# zb_16f628a.net
KiCad netlist of a schematic drawn in Altium Designer
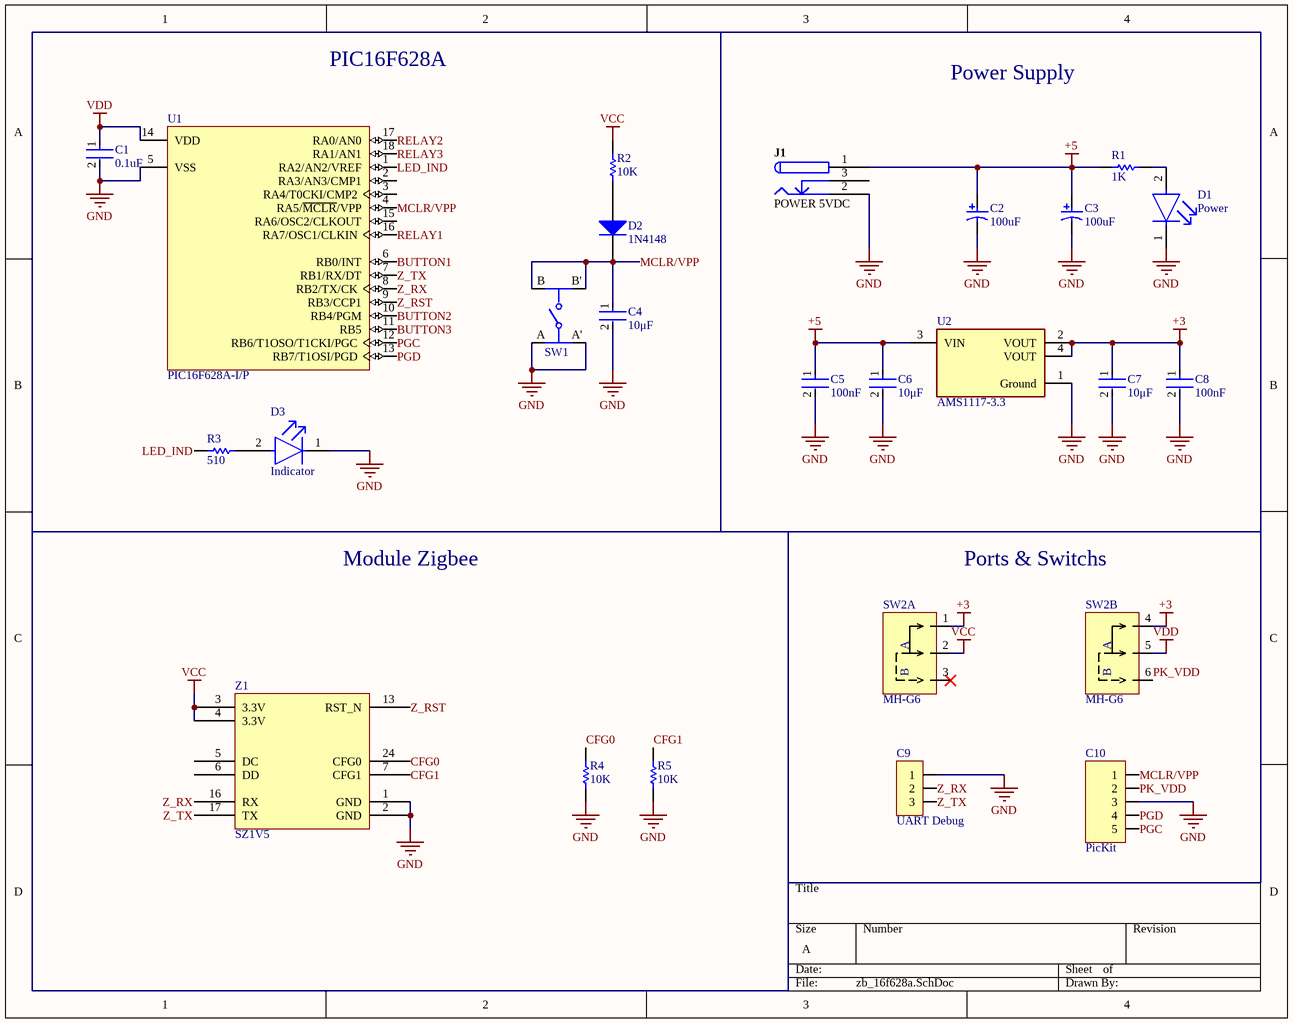
[diagram p0: zb_16f628a.SchDoc]

(export (version "E")
  (design (tool "Eeschema 10.0.6"))
  (components
    (comp (ref "C1")
      (value "0.1uF")
      (footprint "FP-0603-L_1_6_0_15-W_0_81-MFG")
      (description "General Purpose Ceramic Capacitor, 0603, 100nF, 10%, X7R, 15%, 50V")
      (fields (field (name "TOLERANCE") "10%") (field (name "VOLTAGE") "50V"))
      (libsource (lib "Altium Content Vault") (part "02cd4be3c70576c341d710602a673aa"))
    )
    (comp (ref "C2")
      (value "100uF")
      (footprint "PNSC-FK-V-D8_V")
      (fields (field (name "MANUFACTURER") "Panasonic"))
      (libsource (lib "Altium Content Vault") (part "CAP-P-2"))
    )
    (comp (ref "C3")
      (value "100uF")
      (footprint "PNSC-FK-V-D8_V")
      (fields (field (name "MANUFACTURER") "Panasonic"))
      (libsource (lib "Altium Content Vault") (part "CAP-P-2"))
    )
    (comp (ref "C4")
      (value "10μF")
      (footprint "FP-0603-L_1_6_0_15-W_0_81-IPC_A")
      (description "General Purpose Ceramic Capacitor, 0603, 100nF, 10%, X7R, 15%, 50V")
      (fields (field (name "TOLERANCE") "10%") (field (name "VOLTAGE") "50V"))
      (libsource (lib "Altium Content Vault") (part "02cd4be3c70576c341d710602a673aa"))
    )
    (comp (ref "C5")
      (value "100nF")
      (footprint "FP-0603-L_1_6_0_15-W_0_81-IPC_A")
      (description "General Purpose Ceramic Capacitor, 0603, 100nF, 10%, X7R, 15%, 50V")
      (fields (field (name "TOLERANCE") "10%") (field (name "VOLTAGE") "50V"))
      (libsource (lib "Altium Content Vault") (part "02cd4be3c70576c341d710602a673aa"))
    )
    (comp (ref "C6")
      (value "10μF")
      (footprint "FP-0603-L_1_6_0_15-W_0_81-IPC_A")
      (description "General Purpose Ceramic Capacitor, 0603, 100nF, 10%, X7R, 15%, 50V")
      (fields (field (name "TOLERANCE") "10%") (field (name "VOLTAGE") "50V"))
      (libsource (lib "Altium Content Vault") (part "02cd4be3c70576c341d710602a673aa"))
    )
    (comp (ref "C7")
      (value "10μF")
      (footprint "FP-0603-L_1_6_0_15-W_0_81-IPC_A")
      (description "General Purpose Ceramic Capacitor, 0603, 100nF, 10%, X7R, 15%, 50V")
      (fields (field (name "TOLERANCE") "10%") (field (name "VOLTAGE") "50V"))
      (libsource (lib "Altium Content Vault") (part "02cd4be3c70576c341d710602a673aa"))
    )
    (comp (ref "C8")
      (value "100nF")
      (footprint "FP-0603-L_1_6_0_15-W_0_81-IPC_A")
      (description "General Purpose Ceramic Capacitor, 0603, 100nF, 10%, X7R, 15%, 50V")
      (fields (field (name "TOLERANCE") "10%") (field (name "VOLTAGE") "50V"))
      (libsource (lib "Altium Content Vault") (part "02cd4be3c70576c341d710602a673aa"))
    )
    (comp (ref "C9")
      (value "UART Debug")
      (footprint "JP3-D1C")
      (description "WR-PHD 2.54 mm Angled Socket Header")
      (fields
        (field (name "MANUFACTURER") "Würth Elektronik eiSos GmbH")
        (field (name "PARTNO") "613003143121")
        (field (name "CREATED BY") "Karrer Zheng")
      )
      (libsource (lib "TechMT.VN_Lib_Project v2") (part "JP3"))
    )
    (comp (ref "C10")
      (value "PicKit")
      (footprint "JP5-D1C")
      (description "WR-PHD 2.54 mm Angled Socket Header")
      (fields
        (field (name "MANUFACTURER") "Würth Elektronik eiSos GmbH")
        (field (name "PARTNO") "613005143121")
        (field (name "CREATED BY") "Karrer Zheng")
      )
      (libsource (lib "TechMT.VN_Lib_Project v2") (part "JP5"))
    )
    (comp (ref "D1")
      (value "Power")
      (footprint "FP-HLMP-4700-MFG")
      (description "LED RED DIFFUSED T-1 3/4 T/H")
      (fields
        (field (name "OCTOPART") "https://octopart.com/hlmp-4700-broadcom-71130526")
        (field (name "MANUFACTURER") "Broadcom")
      )
      (libsource (lib "Altium Content Vault") (part "8706943c75ba83719d021d2fdc84c58"))
    )
    (comp (ref "D2")
      (value "1N4148")
      (footprint "NXP-SOD27-2_V")
      (description "High-speed Diode, 100 V, 450 mA, 2-Pin SOD27, RoHS")
      (fields (field (name "MANUFACTURER") "NXP Semiconductors"))
      (libsource (lib "Altium Content Vault") (part "NXP-A1K2-2"))
    )
    (comp (ref "D3")
      (value "Indicator")
      (footprint "FP-HLMP-4700-MFG")
      (description "LED RED DIFFUSED T-1 3/4 T/H")
      (fields
        (field (name "OCTOPART") "https://octopart.com/hlmp-4700-broadcom-71130526")
        (field (name "MANUFACTURER") "Broadcom")
      )
      (libsource (lib "Altium Content Vault") (part "8706943c75ba83719d021d2fdc84c58"))
    )
    (comp (ref "J1")
      (value "POWER 5VDC")
      (footprint "KYCN-KLDX-0202-B_V")
      (description "3 Conductor Power Jack, 2 break 2 aux contacts")
      (fields (field (name "PARTNUMBER") "KLDX-0202-B"))
      (libsource (lib "Altium Content Vault") (part "KYCN-KLDX-0202-B-3"))
    )
    (comp (ref "R1")
      (value "1K")
      (footprint "RESC1609X55X30ML15T15")
      (description "Chip Resistor, 10 KOhm, +/- 1%, 0.1 W, -55 to 155 degC, 0603 (1608 Metric), RoHS, Tape and Reel")
      (fields (field (name "TOLERANCE") "1%") (field (name "MANUFACTURER") "Panasonic"))
      (libsource (lib "Altium Content Vault") (part "RES-2"))
    )
    (comp (ref "R2")
      (value "10K")
      (footprint "RESC1609X55X30ML15T15")
      (description "Chip Resistor, 10 KOhm, +/- 1%, 0.1 W, -55 to 155 degC, 0603 (1608 Metric), RoHS, Tape and Reel")
      (fields (field (name "TOLERANCE") "1%") (field (name "MANUFACTURER") "Panasonic"))
      (libsource (lib "Altium Content Vault") (part "RES-2"))
    )
    (comp (ref "R3")
      (value "510")
      (footprint "RESC1609X55X30ML15T15")
      (description "Chip Resistor, 10 KOhm, +/- 1%, 0.1 W, -55 to 155 degC, 0603 (1608 Metric), RoHS, Tape and Reel")
      (fields (field (name "TOLERANCE") "1%") (field (name "MANUFACTURER") "Panasonic"))
      (libsource (lib "Altium Content Vault") (part "RES-2"))
    )
    (comp (ref "R4")
      (value "10K")
      (footprint "RESC1609X55X30ML15T15")
      (description "Chip Resistor, 10 KOhm, +/- 1%, 0.1 W, -55 to 155 degC, 0603 (1608 Metric), RoHS, Tape and Reel")
      (fields (field (name "TOLERANCE") "1%") (field (name "MANUFACTURER") "Panasonic"))
      (libsource (lib "Altium Content Vault") (part "RES-2"))
    )
    (comp (ref "R5")
      (value "10K")
      (footprint "RESC1609X55X30ML15T15")
      (description "Chip Resistor, 10 KOhm, +/- 1%, 0.1 W, -55 to 155 degC, 0603 (1608 Metric), RoHS, Tape and Reel")
      (fields (field (name "TOLERANCE") "1%") (field (name "MANUFACTURER") "Panasonic"))
      (libsource (lib "Altium Content Vault") (part "RES-2"))
    )
    (comp (ref "SW1")
      (value "RESET")
      (footprint "FP-EVQ-PAG05R-MFG")
      (description "SWITCH TACTILE SPST-NO 0.02A 15V")
      (libsource (lib "Altium Content Vault") (part "841f23923f71b23f3ea0ab5dfb78dcc"))
    )
    (comp (ref "SW2")
      (value "MH-G6")
      (footprint "MH-G6")
      (description "6-pin switch MH-G6 2.54mm")
      (libsource (lib "MH-G6") (part "MH-G6"))
    )
    (comp (ref "U1")
      (value "PIC16F628A-I/P")
      (footprint "PDIP300-P18")
      (libsource (lib "Altium Content Vault") (part "MC-8B-16F627A-IL18"))
    )
    (comp (ref "U2")
      (value "AMS1117-3.3")
      (footprint "FP-AMS1117-IPC_A")
      (description "LDO Voltage Regulators 1A, 3.3V")
      (fields
        (field (name "OCTOPART") "https://octopart.com/ams1117-3.3-advanced+monolithic+systems-25899300")
        (field (name "MANUFACTURER") "Advanced Monolithic Systems")
      )
      (libsource (lib "Altium Content Vault") (part "8bdbb5f8e77002000e30dd2845d0354"))
    )
    (comp (ref "Z1")
      (value "SZ1V5")
      (footprint "SZ1V5 PINOUT MODULE")
      (libsource (lib "SZ1V5") (part "SZ1V5_Alt"))
    )
  )
  (nets
    (net (code "1") (name "+3") (class "Default")
      (node (ref "C7") (pin "1") (pinfunction "1_1") (pintype "passive"))
      (node (ref "C8") (pin "1") (pinfunction "1_1") (pintype "passive"))
      (node (ref "SW2") (pin "1") (pinfunction "A_1") (pintype "passive"))
      (node (ref "SW2") (pin "4") (pinfunction "A_4") (pintype "passive"))
      (node (ref "U2") (pin "2") (pinfunction "VOUT_2") (pintype "passive"))
      (node (ref "U2") (pin "4") (pinfunction "VOUT_4") (pintype "passive"))
    )
    (net (code "2") (name "+5") (class "Default")
      (node (ref "C2") (pin "1") (pinfunction "1_1") (pintype "passive"))
      (node (ref "C3") (pin "1") (pinfunction "1_1") (pintype "passive"))
      (node (ref "C5") (pin "1") (pinfunction "1_1") (pintype "passive"))
      (node (ref "C6") (pin "1") (pinfunction "1_1") (pintype "passive"))
      (node (ref "J1") (pin "1") (pintype "power_in"))
      (node (ref "R1") (pin "2") (pinfunction "2_2") (pintype "passive"))
      (node (ref "U2") (pin "3") (pinfunction "VIN_3") (pintype "power_in"))
    )
    (net (code "3") (name "/BUTTON1") (class "Default")
      (node (ref "U1") (pin "6") (pinfunction "RB0/INT_6") (pintype "bidirectional"))
    )
    (net (code "4") (name "/BUTTON2") (class "Default")
      (node (ref "U1") (pin "10") (pinfunction "RB4/PGM_10") (pintype "bidirectional"))
    )
    (net (code "5") (name "/BUTTON3") (class "Default")
      (node (ref "U1") (pin "11") (pinfunction "RB5_11") (pintype "bidirectional"))
    )
    (net (code "6") (name "/CFG0") (class "Default")
      (node (ref "R4") (pin "2") (pinfunction "2_2") (pintype "passive"))
      (node (ref "Z1") (pin "24") (pinfunction "CFG0_24") (pintype "passive"))
    )
    (net (code "7") (name "/CFG1") (class "Default")
      (node (ref "R5") (pin "2") (pinfunction "2_2") (pintype "passive"))
      (node (ref "Z1") (pin "7") (pinfunction "CFG1_7") (pintype "passive"))
    )
    (net (code "8") (name "/LED_IND") (class "Default")
      (node (ref "R3") (pin "2") (pinfunction "2_2") (pintype "passive"))
      (node (ref "U1") (pin "1") (pinfunction "RA2/AN2/VREF_1") (pintype "bidirectional"))
    )
    (net (code "9") (name "/MCLR{slash}VPP") (class "Default")
      (node (ref "C10") (pin "1") (pinfunction "1_1") (pintype "passive"))
      (node (ref "C4") (pin "1") (pinfunction "1_1") (pintype "passive"))
      (node (ref "D2") (pin "2") (pinfunction "K_2") (pintype "passive"))
      (node (ref "SW1") (pin "B") (pinfunction "B_B") (pintype "passive"))
      (node (ref "SW1") (pin "B'") (pinfunction "B'_B'") (pintype "passive"))
      (node (ref "U1") (pin "4") (pinfunction "RA5/~{MCLR}/VPP_4") (pintype "bidirectional"))
    )
    (net (code "10") (name "/PGC") (class "Default")
      (node (ref "C10") (pin "5") (pinfunction "5_5") (pintype "passive"))
      (node (ref "U1") (pin "12") (pinfunction "RB6/T1OSO/T1CKI/PGC_12") (pintype "bidirectional"))
    )
    (net (code "11") (name "/PGD") (class "Default")
      (node (ref "C10") (pin "4") (pinfunction "4_4") (pintype "passive"))
      (node (ref "U1") (pin "13") (pinfunction "RB7/T1OSI/PGD_13") (pintype "bidirectional"))
    )
    (net (code "12") (name "/PK_VDD") (class "Default")
      (node (ref "C10") (pin "2") (pinfunction "2_2") (pintype "passive"))
      (node (ref "SW2") (pin "6") (pinfunction "B_6") (pintype "passive"))
    )
    (net (code "13") (name "/RELAY1") (class "Default")
      (node (ref "U1") (pin "16") (pinfunction "RA7/OSC1/CLKIN_16") (pintype "bidirectional"))
    )
    (net (code "14") (name "/RELAY2") (class "Default")
      (node (ref "U1") (pin "17") (pinfunction "RA0/AN0_17") (pintype "bidirectional"))
    )
    (net (code "15") (name "/RELAY3") (class "Default")
      (node (ref "U1") (pin "18") (pinfunction "RA1/AN1_18") (pintype "bidirectional"))
    )
    (net (code "16") (name "/Z_RST") (class "Default")
      (node (ref "U1") (pin "9") (pinfunction "RB3/CCP1_9") (pintype "bidirectional"))
      (node (ref "Z1") (pin "13") (pinfunction "RST_N_13") (pintype "passive"))
    )
    (net (code "17") (name "/Z_RX") (class "Default")
      (node (ref "C9") (pin "2") (pinfunction "2_2") (pintype "passive"))
      (node (ref "U1") (pin "8") (pinfunction "RB2/TX/CK_8") (pintype "bidirectional"))
      (node (ref "Z1") (pin "16") (pinfunction "RX_16") (pintype "passive"))
    )
    (net (code "18") (name "/Z_TX") (class "Default")
      (node (ref "C9") (pin "3") (pinfunction "3_3") (pintype "passive"))
      (node (ref "U1") (pin "7") (pinfunction "RB1/RX/DT_7") (pintype "bidirectional"))
      (node (ref "Z1") (pin "17") (pinfunction "TX_17") (pintype "passive"))
    )
    (net (code "19") (name "GND") (class "Default")
      (node (ref "C1") (pin "2") (pinfunction "2_2") (pintype "passive"))
      (node (ref "C10") (pin "3") (pinfunction "3_3") (pintype "passive"))
      (node (ref "C2") (pin "2") (pinfunction "2_2") (pintype "passive"))
      (node (ref "C3") (pin "2") (pinfunction "2_2") (pintype "passive"))
      (node (ref "C4") (pin "2") (pinfunction "2_2") (pintype "passive"))
      (node (ref "C5") (pin "2") (pinfunction "2_2") (pintype "passive"))
      (node (ref "C6") (pin "2") (pinfunction "2_2") (pintype "passive"))
      (node (ref "C7") (pin "2") (pinfunction "2_2") (pintype "passive"))
      (node (ref "C8") (pin "2") (pinfunction "2_2") (pintype "passive"))
      (node (ref "C9") (pin "1") (pinfunction "1_1") (pintype "passive"))
      (node (ref "D1") (pin "1") (pinfunction "C_1") (pintype "passive"))
      (node (ref "D3") (pin "1") (pinfunction "C_1") (pintype "passive"))
      (node (ref "J1") (pin "2") (pintype "power_in"))
      (node (ref "R4") (pin "1") (pinfunction "1_1") (pintype "passive"))
      (node (ref "R5") (pin "1") (pinfunction "1_1") (pintype "passive"))
      (node (ref "SW1") (pin "A") (pinfunction "A_A") (pintype "passive"))
      (node (ref "SW1") (pin "A'") (pinfunction "A'_A'") (pintype "passive"))
      (node (ref "U1") (pin "5") (pinfunction "VSS_5") (pintype "power_in"))
      (node (ref "U2") (pin "1") (pinfunction "Ground_1") (pintype "power_in"))
      (node (ref "Z1") (pin "1") (pinfunction "GND_1") (pintype "passive"))
      (node (ref "Z1") (pin "2") (pinfunction "GND_2") (pintype "passive"))
    )
    (net (code "20") (name "Net-(D1-A)") (class "Default")
      (node (ref "D1") (pin "2") (pinfunction "A_2") (pintype "passive"))
      (node (ref "R1") (pin "1") (pinfunction "1_1") (pintype "passive"))
    )
    (net (code "21") (name "Net-(D2-A)") (class "Default")
      (node (ref "D2") (pin "1") (pinfunction "A_1") (pintype "passive"))
      (node (ref "R2") (pin "1") (pinfunction "1_1") (pintype "passive"))
    )
    (net (code "22") (name "Net-(D3-A)") (class "Default")
      (node (ref "D3") (pin "2") (pinfunction "A_2") (pintype "passive"))
      (node (ref "R3") (pin "1") (pinfunction "1_1") (pintype "passive"))
    )
    (net (code "23") (name "VCC") (class "Default")
      (node (ref "R2") (pin "2") (pinfunction "2_2") (pintype "passive"))
      (node (ref "SW2") (pin "2") (pinfunction "COM_2") (pintype "passive"))
      (node (ref "Z1") (pin "3") (pinfunction "3.3V_3") (pintype "passive"))
      (node (ref "Z1") (pin "4") (pinfunction "3.3V_4") (pintype "passive"))
    )
    (net (code "24") (name "VDD") (class "Default")
      (node (ref "C1") (pin "1") (pinfunction "1_1") (pintype "passive"))
      (node (ref "SW2") (pin "5") (pinfunction "COM_5") (pintype "passive"))
      (node (ref "U1") (pin "14") (pinfunction "VDD_14") (pintype "power_in"))
    )
    (net (code "25") (name "unconnected-(J1-Pad3)") (class "Default")
      (node (ref "J1") (pin "3") (pintype "power_in"))
    )
    (net (code "26") (name "unconnected-(SW2A-B-Pad3)") (class "Default")
      (node (ref "SW2") (pin "3") (pinfunction "B_3") (pintype "passive+no_connect"))
    )
    (net (code "27") (name "unconnected-(U1-RA3{slash}AN3{slash}CMP1-Pad2)") (class "Default")
      (node (ref "U1") (pin "2") (pinfunction "RA3/AN3/CMP1_2") (pintype "bidirectional"))
    )
    (net (code "28") (name "unconnected-(U1-RA4{slash}T0CKI{slash}CMP2-Pad3)") (class "Default")
      (node (ref "U1") (pin "3") (pinfunction "RA4/T0CKI/CMP2_3") (pintype "bidirectional"))
    )
    (net (code "29") (name "unconnected-(U1-RA6{slash}OSC2{slash}CLKOUT-Pad15)") (class "Default")
      (node (ref "U1") (pin "15") (pinfunction "RA6/OSC2/CLKOUT_15") (pintype "bidirectional"))
    )
    (net (code "30") (name "unconnected-(Z1-DC-Pad5)") (class "Default")
      (node (ref "Z1") (pin "5") (pinfunction "DC_5") (pintype "passive"))
    )
    (net (code "31") (name "unconnected-(Z1-DD-Pad6)") (class "Default")
      (node (ref "Z1") (pin "6") (pinfunction "DD_6") (pintype "passive"))
    )
  )
)
